# 03-DC_DC.net
KiCad netlist of a schematic drawn in Altium Designer
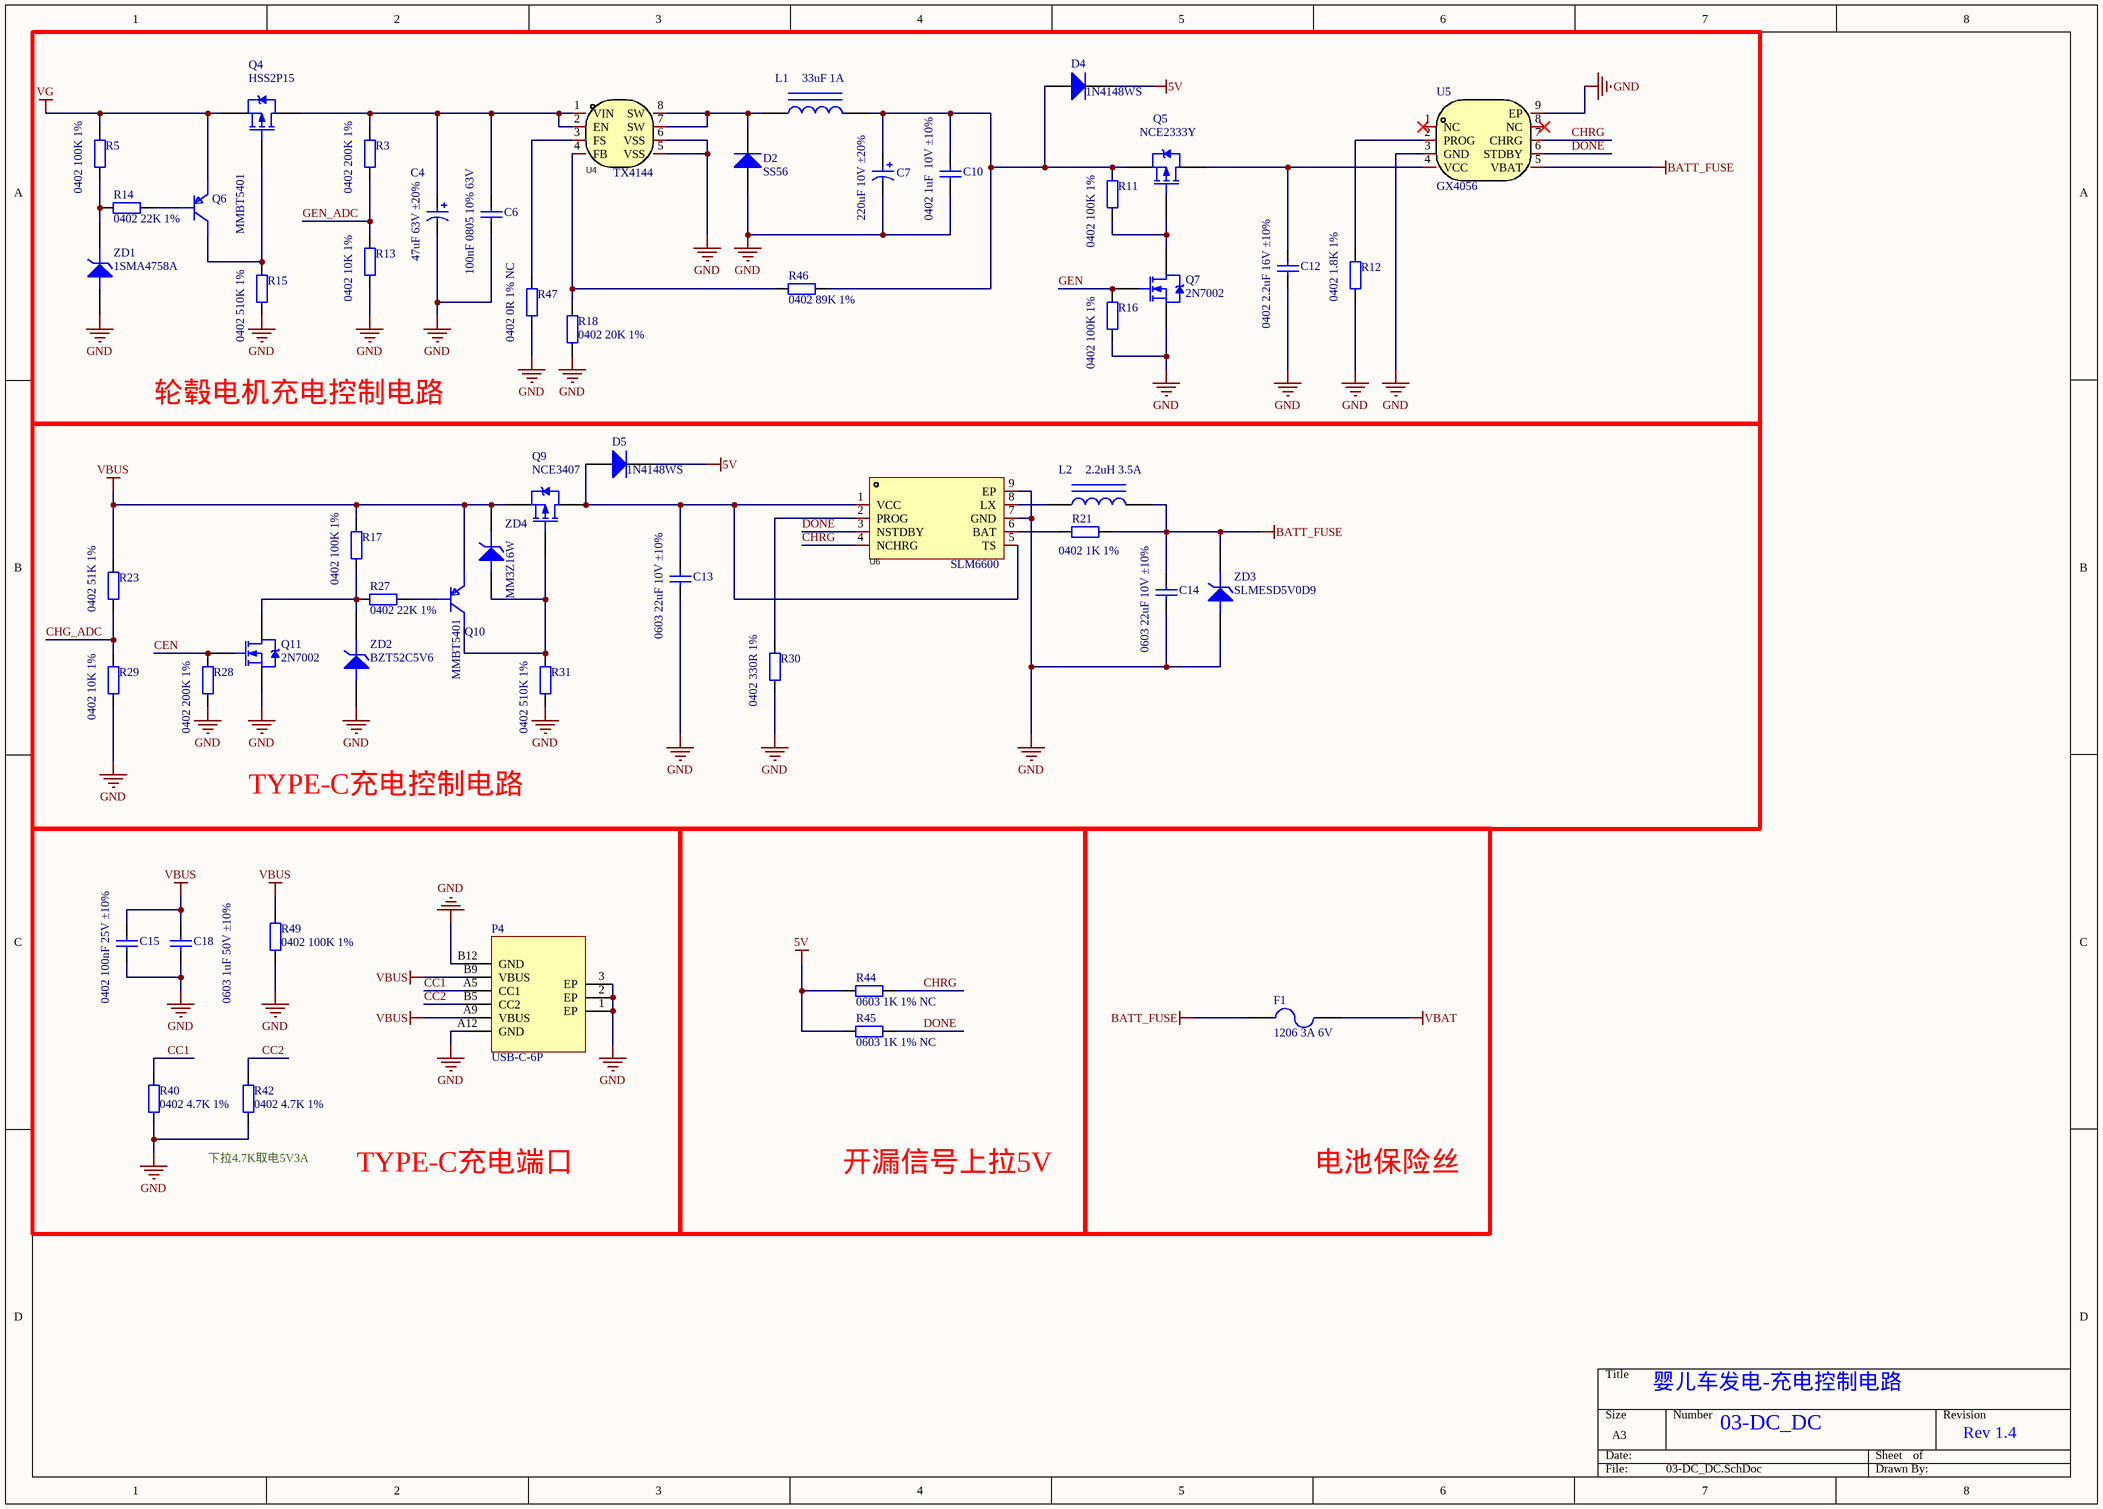
[diagram p0: 03-DC_DC.SchDoc]

(export (version "E")
  (design (tool "Eeschema 10.0.6"))
  (components
    (comp (ref "C4")
      (value "47uF 63V ±20%")
      (footprint "CAP-TH_BD6.3-P2.50-D1.0-WD")
      (description "电解电容")
      (libsource (lib "Hoovic_Library") (part "Cap_elec"))
    )
    (comp (ref "C6")
      (value "100nF 0805 10% 63V")
      (footprint "0805_C")
      (description "贴片电容")
      (libsource (lib "Miscellaneous Devices LC") (part "0805 100nF(104) 10% 50V"))
    )
    (comp (ref "C7")
      (value "220uF 10V ±20%")
      (footprint "CAP-SMD_BD6.3-L6.6-W6.6-LS7.4-FD")
      (description "电解电容")
      (libsource (lib "Hoovic_Library") (part "Cap_elec"))
    )
    (comp (ref "C10")
      (value "0402 1uF  10V ±10%")
      (footprint "C0402")
      (description "贴片电容")
      (libsource (lib "Hoovic_Library") (part "Cap_0402"))
    )
    (comp (ref "C12")
      (value "0402 2.2uF 16V ±10%")
      (footprint "C0402")
      (description "贴片电容")
      (libsource (lib "Hoovic_Library") (part "Cap_0603"))
    )
    (comp (ref "C13")
      (value "0603 22uF 10V ±10%")
      (footprint "C0603")
      (description "贴片电容")
      (libsource (lib "") (part "Cap_0603_1"))
    )
    (comp (ref "C14")
      (value "0603 22uF 10V ±10%")
      (footprint "C0603")
      (description "贴片电容")
      (libsource (lib "") (part "Cap_0603_1"))
    )
    (comp (ref "C15")
      (value "0402 100nF 25V ±10%")
      (footprint "C0402")
      (description "贴片电容")
      (libsource (lib "Hoovic_Library") (part "Cap_0402"))
    )
    (comp (ref "C18")
      (value "0603 1uF 50V ±10%")
      (footprint "C0603")
      (description "贴片电容")
      (libsource (lib "") (part "Cap_0603_1"))
    )
    (comp (ref "D2")
      (value "SS56")
      (footprint "SMB")
      (description "贴片肖特基二极管")
      (libsource (lib "Hoovic_Library") (part "SS56B"))
    )
    (comp (ref "D4")
      (value "1N4148WS")
      (footprint "SOD-323F_L2.0-W1.6-LS2.5-RD")
      (description "贴片普通二极管 Vr=100V Io=150mA Vf=1.25V")
      (libsource (lib "Hoovic_Library") (part "1N4148WS"))
    )
    (comp (ref "D5")
      (value "1N4148WS")
      (footprint "SOD-323F_L2.0-W1.6-LS2.5-RD")
      (description "贴片普通二极管 Vr=100V Io=150mA Vf=1.25V")
      (libsource (lib "Hoovic_Library") (part "1N4148WS"))
    )
    (comp (ref "F1")
      (value "1206 3A 6V")
      (footprint "F1206")
      (description "保险丝/熔断器")
      (libsource (lib "Hoovic_Library") (part "Fuse"))
    )
    (comp (ref "L1")
      (value "33uF 1A")
      (footprint "IND-SMD_L7.1-W6.6")
      (description "功率电感")
      (libsource (lib "Hoovic_Library") (part "Inductor Iron"))
    )
    (comp (ref "L2")
      (value "2.2uH 3.5A")
      (footprint "IND2520")
      (description "功率电感")
      (libsource (lib "Hoovic_Library") (part "Inductor Iron"))
    )
    (comp (ref "P4")
      (value "USB-C-6P")
      (footprint "USB-C-SMD_KH-TYPE-C-6P -L")
      (description "6Pin USB Type-C 接口")
      (libsource (lib "Hoovic_Library") (part "USB-C-6P_"))
    )
    (comp (ref "Q4")
      (value "HSS2P15")
      (footprint "SOT-23-3-MOSFET")
      (description "P-MOSFET with 3 Pin Vdss=60V Id=1.6A Vgs(th)=2V")
      (libsource (lib "Hoovic_Library") (part "NCE2309"))
    )
    (comp (ref "Q5")
      (value "NCE2333Y")
      (footprint "SOT-23-3-MOSFET")
      (description "P-MOSFET with 3 Pin Vdss=60V Id=1.6A Vgs(th)=2V")
      (libsource (lib "Hoovic_Library") (part "NCE2309"))
    )
    (comp (ref "Q6")
      (value "MMBT5401")
      (footprint "SOT-23-3")
      (description "PNP三极管")
      (libsource (lib "Hoovic_Library") (part "MMBT5401"))
    )
    (comp (ref "Q7")
      (value "2N7002")
      (footprint "SOT-23-3-MOSFET")
      (description "N-MOSFET with 3 Pin Vdss=60V  Id=115mA Vgs(th)=2.5V")
      (libsource (lib "Hoovic_Library") (part "2N7002"))
    )
    (comp (ref "Q9")
      (value "NCE3407")
      (footprint "SOT-23-3-MOSFET")
      (description "P-MOSFET with 3 Pin Vdss=60V Id=1.6A Vgs(th)=2V")
      (libsource (lib "Hoovic_Library") (part "NCE2309"))
    )
    (comp (ref "Q10")
      (value "MMBT5401")
      (footprint "SOT-23-3")
      (description "PNP三极管")
      (libsource (lib "Hoovic_Library") (part "MMBT5401"))
    )
    (comp (ref "Q11")
      (value "2N7002")
      (footprint "SOT-23-3-MOSFET")
      (description "N-MOSFET with 3 Pin Vdss=60V  Id=115mA Vgs(th)=2.5V")
      (libsource (lib "Hoovic_Library") (part "2N7002"))
    )
    (comp (ref "R3")
      (value "0402 200K 1%")
      (footprint "R0402")
      (description "贴片电阻")
      (libsource (lib "Hoovic_Library") (part "Res_0402"))
    )
    (comp (ref "R5")
      (value "0402 100K 1%")
      (footprint "R0402")
      (description "贴片电阻")
      (libsource (lib "Hoovic_Library") (part "Res_0402"))
    )
    (comp (ref "R11")
      (value "0402 100K 1%")
      (footprint "R0402")
      (description "贴片电阻")
      (libsource (lib "Hoovic_Library") (part "Res_0402"))
    )
    (comp (ref "R12")
      (value "0402 1.8K 1%")
      (footprint "R0402")
      (description "贴片电阻")
      (libsource (lib "Hoovic_Library") (part "Res_0402"))
    )
    (comp (ref "R13")
      (value "0402 10K 1%")
      (footprint "R0402")
      (description "贴片电阻")
      (libsource (lib "Hoovic_Library") (part "Res_0603"))
    )
    (comp (ref "R14")
      (value "0402 22K 1%")
      (footprint "R0402")
      (description "贴片电阻")
      (libsource (lib "") (part "Res_0402_2"))
    )
    (comp (ref "R15")
      (value "0402 510K 1%")
      (footprint "R0402")
      (description "贴片电阻")
      (libsource (lib "Hoovic_Library") (part "Res_0402"))
    )
    (comp (ref "R16")
      (value "0402 100K 1%")
      (footprint "R0402")
      (description "贴片电阻")
      (libsource (lib "Hoovic_Library") (part "Res_0402"))
    )
    (comp (ref "R17")
      (value "0402 100K 1%")
      (footprint "R0402")
      (description "贴片电阻")
      (libsource (lib "Hoovic_Library") (part "Res_0402"))
    )
    (comp (ref "R18")
      (value "0402 20K 1%")
      (footprint "R0402")
      (description "贴片电阻")
      (libsource (lib "Hoovic_Library") (part "Res_0402"))
    )
    (comp (ref "R21")
      (value "0402 1K 1%")
      (footprint "R0402")
      (description "贴片电阻")
      (libsource (lib "") (part "Res_0402_1"))
    )
    (comp (ref "R23")
      (value "0402 51K 1%")
      (footprint "R0402")
      (description "贴片电阻")
      (libsource (lib "") (part "Res_0603_2"))
    )
    (comp (ref "R27")
      (value "0402 22K 1%")
      (footprint "R0402")
      (description "贴片电阻")
      (libsource (lib "") (part "Res_0402_2"))
    )
    (comp (ref "R28")
      (value "0402 200K 1%")
      (footprint "R0402")
      (description "贴片电阻")
      (libsource (lib "Hoovic_Library") (part "Res_0402"))
    )
    (comp (ref "R29")
      (value "0402 10K 1%")
      (footprint "R0402")
      (description "贴片电阻")
      (libsource (lib "Hoovic_Library") (part "Res_0603"))
    )
    (comp (ref "R30")
      (value "0402 330R 1%")
      (footprint "R0402")
      (description "贴片电阻")
      (libsource (lib "") (part "Res_0402_3"))
    )
    (comp (ref "R31")
      (value "0402 510K 1%")
      (footprint "R0402")
      (description "贴片电阻")
      (libsource (lib "Hoovic_Library") (part "Res_0402"))
    )
    (comp (ref "R40")
      (value "0402 4.7K 1%")
      (footprint "R0402")
      (description "贴片电阻")
      (libsource (lib "") (part "Res_0402_3"))
    )
    (comp (ref "R42")
      (value "0402 4.7K 1%")
      (footprint "R0402")
      (description "贴片电阻")
      (libsource (lib "") (part "Res_0402_3"))
    )
    (comp (ref "R44")
      (value "0603 1K 1% NC")
      (footprint "R0603")
      (description "贴片电阻")
      (libsource (lib "") (part "Res_0603_1"))
    )
    (comp (ref "R45")
      (value "0603 1K 1% NC")
      (footprint "R0603")
      (description "贴片电阻")
      (libsource (lib "") (part "Res_0603_1"))
    )
    (comp (ref "R46")
      (value "0402 89K 1%")
      (footprint "R0402")
      (description "贴片电阻")
      (libsource (lib "") (part "Res_0402_1"))
    )
    (comp (ref "R47")
      (value "0402 0R 1% NC")
      (footprint "R0402")
      (description "贴片电阻")
      (libsource (lib "Hoovic_Library") (part "Res_0402"))
    )
    (comp (ref "R49")
      (value "0402 100K 1%")
      (footprint "R0402")
      (description "贴片电阻")
      (libsource (lib "") (part "Res_0402_3"))
    )
    (comp (ref "U4")
      (value "TX4144")
      (footprint "SOP-8_150mil")
      (description "降压型 输入6V~60V 1.5A")
      (fields (field (name "MANUFACTURER") "XDS(芯鼎盛)"))
      (libsource (lib "Hoovic_Library") (part "TX4144"))
    )
    (comp (ref "U5")
      (value "GX4056")
      (footprint "SOP-8-EP")
      (description "1000mA 锂电池充电器芯片")
      (fields (field (name "MANUFACTURER") "国芯佳品"))
      (libsource (lib "Hoovic_Library") (part "GX4056"))
    )
    (comp (ref "U6")
      (value "SLM6600")
      (footprint "SOP-8_L4.9-W3.9-P1.27-LS6.0-BL-EP")
      (description "锂电池管理")
      (fields (field (name "MANUFACTURER") "无锡松朗微"))
      (libsource (lib "Hoovic_Library") (part "SLM6600"))
    )
    (comp (ref "ZD1")
      (value "1SMA4758A")
      (footprint "SMA")
      (description "稳压管/单向TVS管")
      (libsource (lib "Hoovic_Library") (part "ZENER/TVS"))
    )
    (comp (ref "ZD2")
      (value "BZT52C5V6")
      (footprint "SOD-123")
      (description "稳压管/单向TVS管")
      (libsource (lib "Hoovic_Library") (part "ZENER/TVS"))
    )
    (comp (ref "ZD3")
      (value "SLMESD5V0D9")
      (footprint "SOD-123")
      (description "稳压管/单向TVS管")
      (libsource (lib "Hoovic_Library") (part "ZENER/TVS"))
    )
    (comp (ref "ZD4")
      (value "MM3Z16W")
      (footprint "SOD-323F_L2.0-W1.6-LS2.5-RD")
      (description "稳压管/单向TVS管")
      (libsource (lib "Hoovic_Library") (part "ZENER/TVS"))
    )
  )
  (nets
    (net (code "1") (name "/CC1") (class "Default")
      (node (ref "P4") (pin "A5") (pinfunction "CC1_A5") (pintype "passive"))
      (node (ref "R40") (pin "1") (pinfunction "1_1") (pintype "passive"))
    )
    (net (code "2") (name "/CC2") (class "Default")
      (node (ref "P4") (pin "B5") (pinfunction "CC2_B5") (pintype "passive"))
      (node (ref "R42") (pin "1") (pinfunction "1_1") (pintype "passive"))
    )
    (net (code "3") (name "/CEN") (class "Default")
      (node (ref "Q11") (pin "1") (pinfunction "G_1") (pintype "passive"))
      (node (ref "R28") (pin "2") (pinfunction "2_2") (pintype "passive"))
    )
    (net (code "4") (name "/CHG_ADC") (class "Default")
      (node (ref "R23") (pin "1") (pinfunction "1_1") (pintype "passive"))
      (node (ref "R29") (pin "1") (pinfunction "1_1") (pintype "passive"))
    )
    (net (code "5") (name "/CHRG") (class "Default")
      (node (ref "R44") (pin "2") (pinfunction "2_2") (pintype "passive"))
      (node (ref "U5") (pin "7") (pinfunction "CHRG_7") (pintype "passive"))
      (node (ref "U6") (pin "4") (pinfunction "NCHRG_4") (pintype "passive"))
    )
    (net (code "6") (name "/DONE") (class "Default")
      (node (ref "R45") (pin "2") (pinfunction "2_2") (pintype "passive"))
      (node (ref "U5") (pin "6") (pinfunction "STDBY_6") (pintype "passive"))
      (node (ref "U6") (pin "3") (pinfunction "NSTDBY_3") (pintype "passive"))
    )
    (net (code "7") (name "/GEN") (class "Default")
      (node (ref "Q7") (pin "1") (pinfunction "G_1") (pintype "passive"))
      (node (ref "R16") (pin "2") (pinfunction "2_2") (pintype "passive"))
    )
    (net (code "8") (name "/GEN_ADC") (class "Default")
      (node (ref "R13") (pin "1") (pinfunction "1_1") (pintype "passive"))
      (node (ref "R3") (pin "1") (pinfunction "1_1") (pintype "passive"))
    )
    (net (code "9") (name "5V") (class "Default")
      (node (ref "D4") (pin "1") (pinfunction "K_1") (pintype "passive"))
      (node (ref "D5") (pin "1") (pinfunction "K_1") (pintype "passive"))
      (node (ref "R44") (pin "1") (pinfunction "1_1") (pintype "passive"))
      (node (ref "R45") (pin "1") (pinfunction "1_1") (pintype "passive"))
    )
    (net (code "10") (name "BATT_FUSE") (class "Default")
      (node (ref "C14") (pin "2") (pinfunction "2_2") (pintype "passive"))
      (node (ref "F1") (pin "1") (pinfunction "1_1") (pintype "passive"))
      (node (ref "L2") (pin "2") (pinfunction "2_2") (pintype "passive"))
      (node (ref "R21") (pin "2") (pinfunction "2_2") (pintype "passive"))
      (node (ref "U5") (pin "5") (pinfunction "VBAT_5") (pintype "passive"))
      (node (ref "ZD3") (pin "1") (pinfunction "K_1") (pintype "passive"))
    )
    (net (code "11") (name "GND") (class "Default")
      (node (ref "C10") (pin "1") (pinfunction "1_1") (pintype "passive"))
      (node (ref "C12") (pin "2") (pinfunction "2_2") (pintype "passive"))
      (node (ref "C13") (pin "1") (pinfunction "1_1") (pintype "passive"))
      (node (ref "C14") (pin "1") (pinfunction "1_1") (pintype "passive"))
      (node (ref "C15") (pin "2") (pinfunction "2_2") (pintype "passive"))
      (node (ref "C18") (pin "1") (pinfunction "1_1") (pintype "passive"))
      (node (ref "C4") (pin "2") (pinfunction "2_2") (pintype "passive"))
      (node (ref "C6") (pin "1") (pinfunction "1_1") (pintype "passive"))
      (node (ref "C7") (pin "2") (pinfunction "2_2") (pintype "passive"))
      (node (ref "D2") (pin "2") (pinfunction "A_2") (pintype "passive"))
      (node (ref "P4") (pin "1") (pinfunction "EP_1") (pintype "passive"))
      (node (ref "P4") (pin "2") (pinfunction "EP_2") (pintype "passive"))
      (node (ref "P4") (pin "3") (pinfunction "EP_3") (pintype "passive"))
      (node (ref "P4") (pin "A12") (pinfunction "GND_A12") (pintype "passive"))
      (node (ref "P4") (pin "B12") (pinfunction "GND_B12") (pintype "passive"))
      (node (ref "Q11") (pin "3") (pinfunction "S_3") (pintype "passive"))
      (node (ref "Q7") (pin "3") (pinfunction "S_3") (pintype "passive"))
      (node (ref "R12") (pin "1") (pinfunction "1_1") (pintype "passive"))
      (node (ref "R13") (pin "2") (pinfunction "2_2") (pintype "passive"))
      (node (ref "R15") (pin "1") (pinfunction "1_1") (pintype "passive"))
      (node (ref "R16") (pin "1") (pinfunction "1_1") (pintype "passive"))
      (node (ref "R18") (pin "1") (pinfunction "1_1") (pintype "passive"))
      (node (ref "R28") (pin "1") (pinfunction "1_1") (pintype "passive"))
      (node (ref "R29") (pin "2") (pinfunction "2_2") (pintype "passive"))
      (node (ref "R30") (pin "2") (pinfunction "2_2") (pintype "passive"))
      (node (ref "R31") (pin "1") (pinfunction "1_1") (pintype "passive"))
      (node (ref "R40") (pin "2") (pinfunction "2_2") (pintype "passive"))
      (node (ref "R42") (pin "2") (pinfunction "2_2") (pintype "passive"))
      (node (ref "R47") (pin "1") (pinfunction "1_1") (pintype "passive"))
      (node (ref "R49") (pin "2") (pinfunction "2_2") (pintype "passive"))
      (node (ref "U4") (pin "5") (pinfunction "VSS_5") (pintype "passive"))
      (node (ref "U4") (pin "6") (pinfunction "VSS_6") (pintype "passive"))
      (node (ref "U5") (pin "3") (pinfunction "GND_3") (pintype "passive"))
      (node (ref "U5") (pin "9") (pinfunction "EP_9") (pintype "passive"))
      (node (ref "U6") (pin "7") (pinfunction "GND_7") (pintype "passive"))
      (node (ref "U6") (pin "9") (pinfunction "EP_9") (pintype "passive"))
      (node (ref "ZD1") (pin "2") (pinfunction "A_2") (pintype "passive"))
      (node (ref "ZD2") (pin "2") (pinfunction "A_2") (pintype "passive"))
      (node (ref "ZD3") (pin "2") (pinfunction "A_2") (pintype "passive"))
    )
    (net (code "12") (name "Net-(D2-K)") (class "Default")
      (node (ref "D2") (pin "1") (pinfunction "K_1") (pintype "passive"))
      (node (ref "L1") (pin "1") (pinfunction "1_1") (pintype "passive"))
      (node (ref "U4") (pin "7") (pinfunction "SW_7") (pintype "passive"))
      (node (ref "U4") (pin "8") (pinfunction "SW_8") (pintype "passive"))
    )
    (net (code "13") (name "Net-(D4-A)") (class "Default")
      (node (ref "C10") (pin "2") (pinfunction "2_2") (pintype "passive"))
      (node (ref "C7") (pin "1") (pinfunction "1_1") (pintype "passive"))
      (node (ref "D4") (pin "2") (pinfunction "A_2") (pintype "passive"))
      (node (ref "L1") (pin "2") (pinfunction "2_2") (pintype "passive"))
      (node (ref "Q5") (pin "3") (pinfunction "S_3") (pintype "passive"))
      (node (ref "R11") (pin "2") (pinfunction "2_2") (pintype "passive"))
      (node (ref "R46") (pin "2") (pinfunction "2_2") (pintype "passive"))
    )
    (net (code "14") (name "Net-(D5-A)") (class "Default")
      (node (ref "C13") (pin "2") (pinfunction "2_2") (pintype "passive"))
      (node (ref "D5") (pin "2") (pinfunction "A_2") (pintype "passive"))
      (node (ref "Q9") (pin "2") (pinfunction "D_2") (pintype "passive"))
      (node (ref "U6") (pin "1") (pinfunction "VCC_1") (pintype "passive"))
      (node (ref "U6") (pin "5") (pinfunction "TS_5") (pintype "passive"))
    )
    (net (code "15") (name "Net-(Q4-D)") (class "Default")
      (node (ref "C4") (pin "1") (pinfunction "1_1") (pintype "passive"))
      (node (ref "C6") (pin "2") (pinfunction "2_2") (pintype "passive"))
      (node (ref "Q4") (pin "2") (pinfunction "D_2") (pintype "passive"))
      (node (ref "R3") (pin "2") (pinfunction "2_2") (pintype "passive"))
      (node (ref "U4") (pin "1") (pinfunction "VIN_1") (pintype "passive"))
      (node (ref "U4") (pin "2") (pinfunction "EN_2") (pintype "passive"))
    )
    (net (code "16") (name "Net-(Q4-G)") (class "Default")
      (node (ref "Q4") (pin "1") (pinfunction "G_1") (pintype "passive"))
      (node (ref "Q6") (pin "3") (pinfunction "C_3") (pintype "passive"))
      (node (ref "R15") (pin "2") (pinfunction "2_2") (pintype "passive"))
    )
    (net (code "17") (name "Net-(Q5-D)") (class "Default")
      (node (ref "C12") (pin "1") (pinfunction "1_1") (pintype "passive"))
      (node (ref "Q5") (pin "2") (pinfunction "D_2") (pintype "passive"))
      (node (ref "U5") (pin "4") (pinfunction "VCC_4") (pintype "passive"))
    )
    (net (code "18") (name "Net-(Q5-G)") (class "Default")
      (node (ref "Q5") (pin "1") (pinfunction "G_1") (pintype "passive"))
      (node (ref "Q7") (pin "2") (pinfunction "D_2") (pintype "passive"))
      (node (ref "R11") (pin "1") (pinfunction "1_1") (pintype "passive"))
    )
    (net (code "19") (name "Net-(Q6-B)") (class "Default")
      (node (ref "Q6") (pin "1") (pinfunction "B_1") (pintype "passive"))
      (node (ref "R14") (pin "1") (pinfunction "1_1") (pintype "passive"))
    )
    (net (code "20") (name "Net-(Q10-B)") (class "Default")
      (node (ref "Q10") (pin "1") (pinfunction "B_1") (pintype "passive"))
      (node (ref "R27") (pin "1") (pinfunction "1_1") (pintype "passive"))
    )
    (net (code "21") (name "Net-(Q10-C)") (class "Default")
      (node (ref "Q10") (pin "3") (pinfunction "C_3") (pintype "passive"))
      (node (ref "Q9") (pin "1") (pinfunction "G_1") (pintype "passive"))
      (node (ref "R31") (pin "2") (pinfunction "2_2") (pintype "passive"))
      (node (ref "ZD4") (pin "2") (pinfunction "A_2") (pintype "passive"))
    )
    (net (code "22") (name "Net-(Q11-D)") (class "Default")
      (node (ref "Q11") (pin "2") (pinfunction "D_2") (pintype "passive"))
      (node (ref "R17") (pin "1") (pinfunction "1_1") (pintype "passive"))
      (node (ref "R27") (pin "2") (pinfunction "2_2") (pintype "passive"))
      (node (ref "ZD2") (pin "1") (pinfunction "K_1") (pintype "passive"))
    )
    (net (code "23") (name "Net-(U4-FB)") (class "Default")
      (node (ref "R18") (pin "2") (pinfunction "2_2") (pintype "passive"))
      (node (ref "R46") (pin "1") (pinfunction "1_1") (pintype "passive"))
      (node (ref "U4") (pin "4") (pinfunction "FB_4") (pintype "passive"))
    )
    (net (code "24") (name "Net-(U4-FS)") (class "Default")
      (node (ref "R47") (pin "2") (pinfunction "2_2") (pintype "passive"))
      (node (ref "U4") (pin "3") (pinfunction "FS_3") (pintype "passive"))
    )
    (net (code "25") (name "Net-(U5-PROG)") (class "Default")
      (node (ref "R12") (pin "2") (pinfunction "2_2") (pintype "passive"))
      (node (ref "U5") (pin "2") (pinfunction "PROG_2") (pintype "passive"))
    )
    (net (code "26") (name "Net-(U6-BAT)") (class "Default")
      (node (ref "R21") (pin "1") (pinfunction "1_1") (pintype "passive"))
      (node (ref "U6") (pin "6") (pinfunction "BAT_6") (pintype "passive"))
    )
    (net (code "27") (name "Net-(U6-LX)") (class "Default")
      (node (ref "L2") (pin "1") (pinfunction "1_1") (pintype "passive"))
      (node (ref "U6") (pin "8") (pinfunction "LX_8") (pintype "passive"))
    )
    (net (code "28") (name "Net-(U6-PROG)") (class "Default")
      (node (ref "R30") (pin "1") (pinfunction "1_1") (pintype "passive"))
      (node (ref "U6") (pin "2") (pinfunction "PROG_2") (pintype "passive"))
    )
    (net (code "29") (name "Net-(ZD1-K)") (class "Default")
      (node (ref "R14") (pin "2") (pinfunction "2_2") (pintype "passive"))
      (node (ref "R5") (pin "1") (pinfunction "1_1") (pintype "passive"))
      (node (ref "ZD1") (pin "1") (pinfunction "K_1") (pintype "passive"))
    )
    (net (code "30") (name "VBAT") (class "Default")
      (node (ref "F1") (pin "2") (pinfunction "2_2") (pintype "passive"))
    )
    (net (code "31") (name "VBUS") (class "Default")
      (node (ref "C15") (pin "1") (pinfunction "1_1") (pintype "passive"))
      (node (ref "C18") (pin "2") (pinfunction "2_2") (pintype "passive"))
      (node (ref "P4") (pin "A9") (pinfunction "VBUS_A9") (pintype "passive"))
      (node (ref "P4") (pin "B9") (pinfunction "VBUS_B9") (pintype "passive"))
      (node (ref "Q10") (pin "2") (pinfunction "E_2") (pintype "passive"))
      (node (ref "Q9") (pin "3") (pinfunction "S_3") (pintype "passive"))
      (node (ref "R17") (pin "2") (pinfunction "2_2") (pintype "passive"))
      (node (ref "R23") (pin "2") (pinfunction "2_2") (pintype "passive"))
      (node (ref "R49") (pin "1") (pinfunction "1_1") (pintype "passive"))
      (node (ref "ZD4") (pin "1") (pinfunction "K_1") (pintype "passive"))
    )
    (net (code "32") (name "VG") (class "Default")
      (node (ref "Q4") (pin "3") (pinfunction "S_3") (pintype "passive"))
      (node (ref "Q6") (pin "2") (pinfunction "E_2") (pintype "passive"))
      (node (ref "R5") (pin "2") (pinfunction "2_2") (pintype "passive"))
    )
    (net (code "33") (name "unconnected-(U5-NC-Pad1)") (class "Default")
      (node (ref "U5") (pin "1") (pinfunction "NC_1") (pintype "passive+no_connect"))
    )
    (net (code "34") (name "unconnected-(U5-NC-Pad8)") (class "Default")
      (node (ref "U5") (pin "8") (pinfunction "NC_8") (pintype "passive+no_connect"))
    )
  )
)
